# Breakout_20Pin_Wide.net
KiCad netlist of a schematic drawn in EAGLE
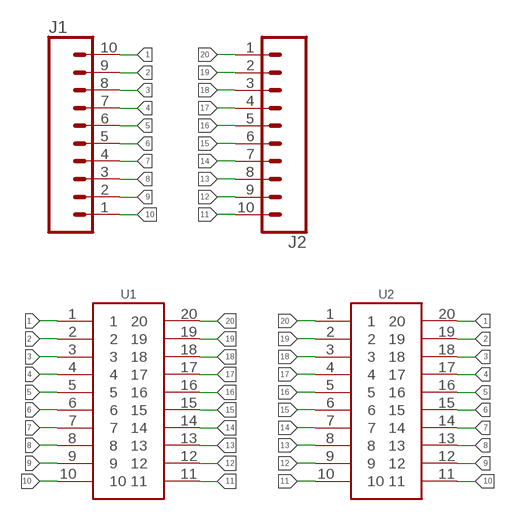
[diagram p0: schematic, sheet 1]

(export (version "E")
  (design (tool "Eeschema 10.0.6"))
  (components
    (comp (ref "J1")
      (value "CONN_10\"")
      (footprint "eagle-import:1X10")
      (libsource (lib "eagle-import") (part "CONN_10{dblquote}"))
    )
    (comp (ref "J2")
      (value "CONN_10\"")
      (footprint "eagle-import:1X10")
      (libsource (lib "eagle-import") (part "CONN_10{dblquote}"))
    )
    (comp (ref "U1")
      (value "GEN_20SOIC_W")
      (footprint "eagle-import:SO-20DW")
      (libsource (lib "eagle-import") (part "GEN_20SOIC_W"))
    )
    (comp (ref "U2")
      (value "GEN_20SSOP")
      (footprint "eagle-import:SSOP20")
      (libsource (lib "eagle-import") (part "GEN_20SSOP"))
    )
  )
  (nets
    (net (code "1") (name "1") (class "Default")
      (node (ref "J1") (pin "10") (pinfunction "10_10") (pintype "passive"))
      (node (ref "U1") (pin "1") (pinfunction "1_1") (pintype "bidirectional"))
      (node (ref "U2") (pin "20") (pinfunction "20_20") (pintype "bidirectional"))
    )
    (net (code "2") (name "2") (class "Default")
      (node (ref "J1") (pin "9") (pinfunction "9_9") (pintype "passive"))
      (node (ref "U1") (pin "2") (pinfunction "2_2") (pintype "bidirectional"))
      (node (ref "U2") (pin "19") (pinfunction "19_19") (pintype "bidirectional"))
    )
    (net (code "3") (name "3") (class "Default")
      (node (ref "J1") (pin "8") (pinfunction "8_8") (pintype "passive"))
      (node (ref "U1") (pin "3") (pinfunction "3_3") (pintype "bidirectional"))
      (node (ref "U2") (pin "18") (pinfunction "18_18") (pintype "bidirectional"))
    )
    (net (code "4") (name "4") (class "Default")
      (node (ref "J1") (pin "7") (pinfunction "7_7") (pintype "passive"))
      (node (ref "U1") (pin "4") (pinfunction "4_4") (pintype "bidirectional"))
      (node (ref "U2") (pin "17") (pinfunction "17_17") (pintype "bidirectional"))
    )
    (net (code "5") (name "5") (class "Default")
      (node (ref "J1") (pin "6") (pinfunction "6_6") (pintype "passive"))
      (node (ref "U1") (pin "5") (pinfunction "5_5") (pintype "bidirectional"))
      (node (ref "U2") (pin "16") (pinfunction "16_16") (pintype "bidirectional"))
    )
    (net (code "6") (name "6") (class "Default")
      (node (ref "J1") (pin "5") (pinfunction "5_5") (pintype "passive"))
      (node (ref "U1") (pin "6") (pinfunction "6_6") (pintype "bidirectional"))
      (node (ref "U2") (pin "15") (pinfunction "15_15") (pintype "bidirectional"))
    )
    (net (code "7") (name "7") (class "Default")
      (node (ref "J1") (pin "4") (pinfunction "4_4") (pintype "passive"))
      (node (ref "U1") (pin "7") (pinfunction "7_7") (pintype "bidirectional"))
      (node (ref "U2") (pin "14") (pinfunction "14_14") (pintype "bidirectional"))
    )
    (net (code "8") (name "8") (class "Default")
      (node (ref "J1") (pin "3") (pinfunction "3_3") (pintype "passive"))
      (node (ref "U1") (pin "8") (pinfunction "8_8") (pintype "bidirectional"))
      (node (ref "U2") (pin "13") (pinfunction "13_13") (pintype "bidirectional"))
    )
    (net (code "9") (name "9") (class "Default")
      (node (ref "J1") (pin "2") (pinfunction "2_2") (pintype "passive"))
      (node (ref "U1") (pin "9") (pinfunction "9_9") (pintype "bidirectional"))
      (node (ref "U2") (pin "12") (pinfunction "12_12") (pintype "bidirectional"))
    )
    (net (code "10") (name "10") (class "Default")
      (node (ref "J1") (pin "1") (pinfunction "1_1") (pintype "passive"))
      (node (ref "U1") (pin "10") (pinfunction "10_10") (pintype "bidirectional"))
      (node (ref "U2") (pin "11") (pinfunction "11_11") (pintype "bidirectional"))
    )
    (net (code "11") (name "11") (class "Default")
      (node (ref "J2") (pin "10") (pinfunction "10_10") (pintype "passive"))
      (node (ref "U1") (pin "11") (pinfunction "11_11") (pintype "bidirectional"))
      (node (ref "U2") (pin "10") (pinfunction "10_10") (pintype "bidirectional"))
    )
    (net (code "12") (name "12") (class "Default")
      (node (ref "J2") (pin "9") (pinfunction "9_9") (pintype "passive"))
      (node (ref "U1") (pin "12") (pinfunction "12_12") (pintype "bidirectional"))
      (node (ref "U2") (pin "9") (pinfunction "9_9") (pintype "bidirectional"))
    )
    (net (code "13") (name "13") (class "Default")
      (node (ref "J2") (pin "8") (pinfunction "8_8") (pintype "passive"))
      (node (ref "U1") (pin "13") (pinfunction "13_13") (pintype "bidirectional"))
      (node (ref "U2") (pin "8") (pinfunction "8_8") (pintype "bidirectional"))
    )
    (net (code "14") (name "14") (class "Default")
      (node (ref "J2") (pin "7") (pinfunction "7_7") (pintype "passive"))
      (node (ref "U1") (pin "14") (pinfunction "14_14") (pintype "bidirectional"))
      (node (ref "U2") (pin "7") (pinfunction "7_7") (pintype "bidirectional"))
    )
    (net (code "15") (name "15") (class "Default")
      (node (ref "J2") (pin "6") (pinfunction "6_6") (pintype "passive"))
      (node (ref "U1") (pin "15") (pinfunction "15_15") (pintype "bidirectional"))
      (node (ref "U2") (pin "6") (pinfunction "6_6") (pintype "bidirectional"))
    )
    (net (code "16") (name "16") (class "Default")
      (node (ref "J2") (pin "5") (pinfunction "5_5") (pintype "passive"))
      (node (ref "U1") (pin "16") (pinfunction "16_16") (pintype "bidirectional"))
      (node (ref "U2") (pin "5") (pinfunction "5_5") (pintype "bidirectional"))
    )
    (net (code "17") (name "17") (class "Default")
      (node (ref "J2") (pin "4") (pinfunction "4_4") (pintype "passive"))
      (node (ref "U1") (pin "17") (pinfunction "17_17") (pintype "bidirectional"))
      (node (ref "U2") (pin "4") (pinfunction "4_4") (pintype "bidirectional"))
    )
    (net (code "18") (name "18") (class "Default")
      (node (ref "J2") (pin "3") (pinfunction "3_3") (pintype "passive"))
      (node (ref "U1") (pin "18") (pinfunction "18_18") (pintype "bidirectional"))
      (node (ref "U2") (pin "3") (pinfunction "3_3") (pintype "bidirectional"))
    )
    (net (code "19") (name "19") (class "Default")
      (node (ref "J2") (pin "2") (pinfunction "2_2") (pintype "passive"))
      (node (ref "U1") (pin "19") (pinfunction "19_19") (pintype "bidirectional"))
      (node (ref "U2") (pin "2") (pinfunction "2_2") (pintype "bidirectional"))
    )
    (net (code "20") (name "20") (class "Default")
      (node (ref "J2") (pin "1") (pinfunction "1_1") (pintype "passive"))
      (node (ref "U1") (pin "20") (pinfunction "20_20") (pintype "bidirectional"))
      (node (ref "U2") (pin "1") (pinfunction "1_1") (pintype "bidirectional"))
    )
  )
)
